# Sensor_interfacing.net
KiCad netlist of a schematic drawn in Altium Designer
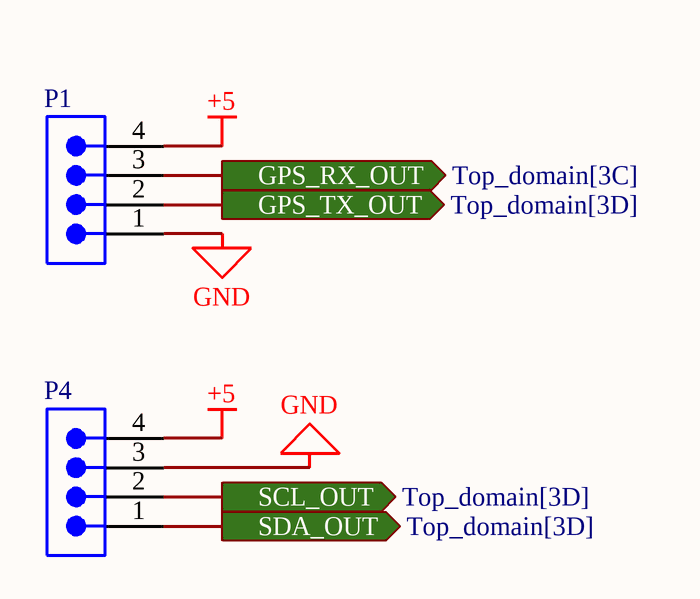
[diagram p0: Sensor_interfacing.SchDoc]

(export (version "E")
  (design (tool "Eeschema 10.0.6"))
  (components
    (comp (ref "P1")
      (value "61300411121")
      (footprint "61300411121")
      (libsource (lib "Altium Content Vault") (part "Header_Male_1R_04P"))
    )
    (comp (ref "P4")
      (value "61300411121")
      (footprint "61300411121")
      (libsource (lib "Altium Content Vault") (part "Header_Male_1R_04P"))
    )
  )
  (nets
    (net (code "1") (name "+5") (class "Default")
      (node (ref "P1") (pin "4") (pinfunction "4_4") (pintype "passive"))
      (node (ref "P4") (pin "4") (pinfunction "4_4") (pintype "passive"))
    )
    (net (code "2") (name "/GPS_RX_OUT") (class "Default")
      (node (ref "P1") (pin "3") (pinfunction "3_3") (pintype "passive"))
    )
    (net (code "3") (name "/GPS_TX_OUT") (class "Default")
      (node (ref "P1") (pin "2") (pinfunction "2_2") (pintype "passive"))
    )
    (net (code "4") (name "/SCL_OUT") (class "Default")
      (node (ref "P4") (pin "2") (pinfunction "2_2") (pintype "passive"))
    )
    (net (code "5") (name "/SDA_OUT") (class "Default")
      (node (ref "P4") (pin "1") (pinfunction "1_1") (pintype "passive"))
    )
    (net (code "6") (name "GND") (class "Default")
      (node (ref "P1") (pin "1") (pinfunction "1_1") (pintype "passive"))
      (node (ref "P4") (pin "3") (pinfunction "3_3") (pintype "passive"))
    )
  )
)
